# Sheet1.net
KiCad netlist of a schematic drawn in Altium Designer
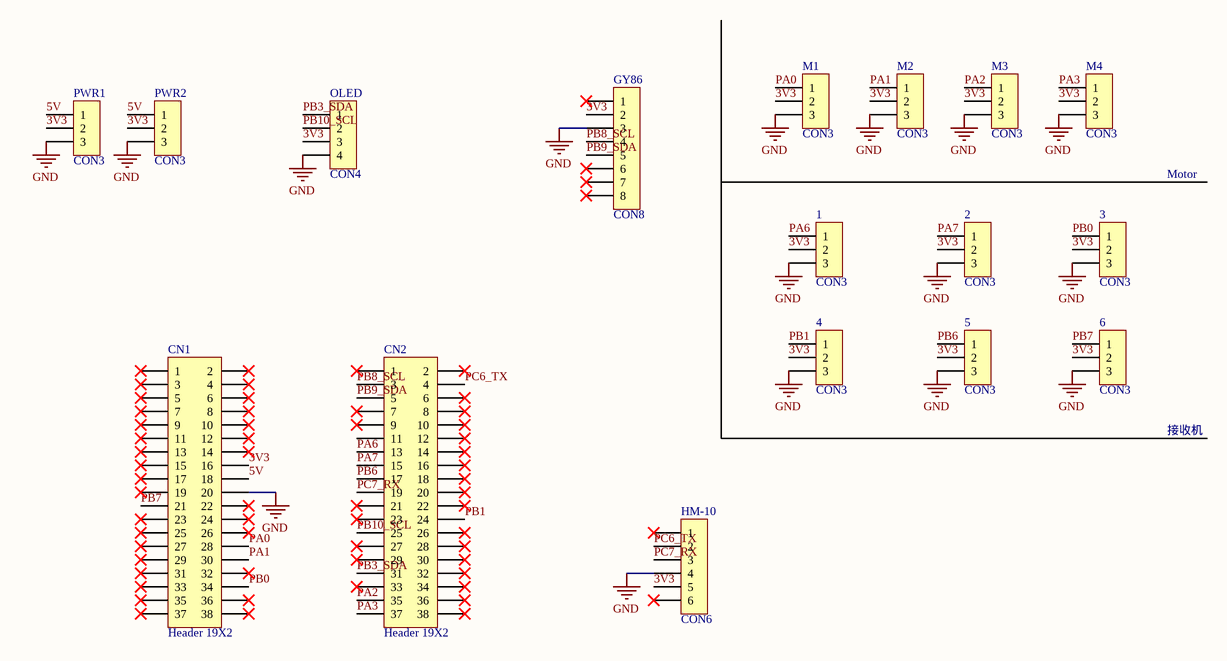
[diagram p0: Sheet1.SchDoc]

(export (version "E")
  (design (tool "Eeschema 10.0.6"))
  (components
    (comp (ref "1") (value "CON3") (footprint "HDR2.54-M-LI-3P") (libsource (lib "常用元件库") (part "CON3")))
    (comp (ref "2") (value "CON3") (footprint "HDR2.54-M-LI-3P") (libsource (lib "常用元件库") (part "CON3")))
    (comp (ref "3") (value "CON3") (footprint "HDR2.54-M-LI-3P") (libsource (lib "常用元件库") (part "CON3")))
    (comp (ref "4") (value "CON3") (footprint "HDR2.54-M-LI-3P") (libsource (lib "常用元件库") (part "CON3")))
    (comp (ref "5") (value "CON3") (footprint "HDR2.54-M-LI-3P") (libsource (lib "常用元件库") (part "CON3")))
    (comp (ref "6") (value "CON3") (footprint "HDR2.54-M-LI-3P") (libsource (lib "常用元件库") (part "CON3")))
    (comp (ref "CN1")
      (value "Header 19X2")
      (footprint "HDR2.54-LI-2x19P")
      (description "Header, 19-Pin, Dual row")
      (fields (field (name "PUBLISHER") "Altium Limited"))
      (libsource (lib "Nucleo_64_1") (part "Header 19X2"))
    )
    (comp (ref "CN2")
      (value "Header 19X2")
      (footprint "HDR2.54-LI-2x19P")
      (description "Header, 19-Pin, Dual row")
      (fields (field (name "PUBLISHER") "Altium Limited"))
      (libsource (lib "Nucleo_64_1") (part "Header 19X2"))
    )
    (comp (ref "GY86") (value "CON8") (footprint "HDR2.54-M-LI-8P") (libsource (lib "常用元件库") (part "CON8")))
    (comp (ref "HM-10") (value "CON6") (footprint "HDR2.54-M-LI-6P") (libsource (lib "常用元件库") (part "CON6")))
    (comp (ref "M1") (value "CON3") (footprint "HDR2.54-M-LI-3P") (libsource (lib "常用元件库") (part "CON3")))
    (comp (ref "M2") (value "CON3") (footprint "HDR2.54-M-LI-3P") (libsource (lib "常用元件库") (part "CON3")))
    (comp (ref "M3") (value "CON3") (footprint "HDR2.54-M-LI-3P") (libsource (lib "常用元件库") (part "CON3")))
    (comp (ref "M4") (value "CON3") (footprint "HDR2.54-M-LI-3P") (libsource (lib "常用元件库") (part "CON3")))
    (comp (ref "OLED") (value "CON4") (footprint "HDR2.54-M-LI-4P") (libsource (lib "常用元件库") (part "CON4")))
    (comp (ref "PWR1") (value "CON3") (footprint "HDR2.54-M-LI-3P") (libsource (lib "常用元件库") (part "CON3")))
    (comp (ref "PWR2") (value "CON3") (footprint "HDR2.54-M-LI-3P") (libsource (lib "常用元件库") (part "CON3")))
  )
  (nets
    (net (code "1") (name "/3V3") (class "Default")
      (node (ref "1") (pin "2") (pinfunction "2_2") (pintype "passive"))
      (node (ref "2") (pin "2") (pinfunction "2_2") (pintype "passive"))
      (node (ref "3") (pin "2") (pinfunction "2_2") (pintype "passive"))
      (node (ref "4") (pin "2") (pinfunction "2_2") (pintype "passive"))
      (node (ref "5") (pin "2") (pinfunction "2_2") (pintype "passive"))
      (node (ref "6") (pin "2") (pinfunction "2_2") (pintype "passive"))
      (node (ref "CN1") (pin "16") (pinfunction "16_16") (pintype "passive"))
      (node (ref "GY86") (pin "2") (pinfunction "2_2") (pintype "passive"))
      (node (ref "HM-10") (pin "5") (pinfunction "5_5") (pintype "passive"))
      (node (ref "M1") (pin "2") (pinfunction "2_2") (pintype "passive"))
      (node (ref "M2") (pin "2") (pinfunction "2_2") (pintype "passive"))
      (node (ref "M3") (pin "2") (pinfunction "2_2") (pintype "passive"))
      (node (ref "M4") (pin "2") (pinfunction "2_2") (pintype "passive"))
      (node (ref "OLED") (pin "3") (pinfunction "3_3") (pintype "passive"))
      (node (ref "PWR1") (pin "2") (pinfunction "2_2") (pintype "passive"))
      (node (ref "PWR2") (pin "2") (pinfunction "2_2") (pintype "passive"))
    )
    (net (code "2") (name "/5V") (class "Default")
      (node (ref "CN1") (pin "18") (pinfunction "18_18") (pintype "passive"))
      (node (ref "PWR1") (pin "1") (pinfunction "1_1") (pintype "passive"))
      (node (ref "PWR2") (pin "1") (pinfunction "1_1") (pintype "passive"))
    )
    (net (code "3") (name "/PA0") (class "Default")
      (node (ref "CN1") (pin "28") (pinfunction "28_28") (pintype "passive"))
      (node (ref "M1") (pin "1") (pinfunction "1_1") (pintype "passive"))
    )
    (net (code "4") (name "/PA1") (class "Default")
      (node (ref "CN1") (pin "30") (pinfunction "30_30") (pintype "passive"))
      (node (ref "M2") (pin "1") (pinfunction "1_1") (pintype "passive"))
    )
    (net (code "5") (name "/PA2") (class "Default")
      (node (ref "CN2") (pin "35") (pinfunction "35_35") (pintype "passive"))
      (node (ref "M3") (pin "1") (pinfunction "1_1") (pintype "passive"))
    )
    (net (code "6") (name "/PA3") (class "Default")
      (node (ref "CN2") (pin "37") (pinfunction "37_37") (pintype "passive"))
      (node (ref "M4") (pin "1") (pinfunction "1_1") (pintype "passive"))
    )
    (net (code "7") (name "/PA6") (class "Default")
      (node (ref "1") (pin "1") (pinfunction "1_1") (pintype "passive"))
      (node (ref "CN2") (pin "13") (pinfunction "13_13") (pintype "passive"))
    )
    (net (code "8") (name "/PA7") (class "Default")
      (node (ref "2") (pin "1") (pinfunction "1_1") (pintype "passive"))
      (node (ref "CN2") (pin "15") (pinfunction "15_15") (pintype "passive"))
    )
    (net (code "9") (name "/PB0") (class "Default")
      (node (ref "3") (pin "1") (pinfunction "1_1") (pintype "passive"))
      (node (ref "CN1") (pin "34") (pinfunction "34_34") (pintype "passive"))
    )
    (net (code "10") (name "/PB1") (class "Default")
      (node (ref "4") (pin "1") (pinfunction "1_1") (pintype "passive"))
      (node (ref "CN2") (pin "24") (pinfunction "24_24") (pintype "passive"))
    )
    (net (code "11") (name "/PB3_SDA") (class "Default")
      (node (ref "CN2") (pin "31") (pinfunction "31_31") (pintype "passive"))
      (node (ref "OLED") (pin "1") (pinfunction "1_1") (pintype "passive"))
    )
    (net (code "12") (name "/PB6") (class "Default")
      (node (ref "5") (pin "1") (pinfunction "1_1") (pintype "passive"))
      (node (ref "CN2") (pin "17") (pinfunction "17_17") (pintype "passive"))
    )
    (net (code "13") (name "/PB7") (class "Default")
      (node (ref "6") (pin "1") (pinfunction "1_1") (pintype "passive"))
      (node (ref "CN1") (pin "21") (pinfunction "21_21") (pintype "passive"))
    )
    (net (code "14") (name "/PB8_SCL") (class "Default")
      (node (ref "CN2") (pin "3") (pinfunction "3_3") (pintype "passive"))
      (node (ref "GY86") (pin "4") (pinfunction "4_4") (pintype "passive"))
    )
    (net (code "15") (name "/PB9_SDA") (class "Default")
      (node (ref "CN2") (pin "5") (pinfunction "5_5") (pintype "passive"))
      (node (ref "GY86") (pin "5") (pinfunction "5_5") (pintype "passive"))
    )
    (net (code "16") (name "/PB10_SCL") (class "Default")
      (node (ref "CN2") (pin "25") (pinfunction "25_25") (pintype "passive"))
      (node (ref "OLED") (pin "2") (pinfunction "2_2") (pintype "passive"))
    )
    (net (code "17") (name "/PC6_TX") (class "Default")
      (node (ref "CN2") (pin "4") (pinfunction "4_4") (pintype "passive"))
      (node (ref "HM-10") (pin "2") (pinfunction "2_2") (pintype "passive"))
    )
    (net (code "18") (name "/PC7_RX") (class "Default")
      (node (ref "CN2") (pin "19") (pinfunction "19_19") (pintype "passive"))
      (node (ref "HM-10") (pin "3") (pinfunction "3_3") (pintype "passive"))
    )
    (net (code "19") (name "GND") (class "Default")
      (node (ref "1") (pin "3") (pinfunction "3_3") (pintype "passive"))
      (node (ref "2") (pin "3") (pinfunction "3_3") (pintype "passive"))
      (node (ref "3") (pin "3") (pinfunction "3_3") (pintype "passive"))
      (node (ref "4") (pin "3") (pinfunction "3_3") (pintype "passive"))
      (node (ref "5") (pin "3") (pinfunction "3_3") (pintype "passive"))
      (node (ref "6") (pin "3") (pinfunction "3_3") (pintype "passive"))
      (node (ref "CN1") (pin "20") (pinfunction "20_20") (pintype "passive"))
      (node (ref "GY86") (pin "3") (pinfunction "3_3") (pintype "passive"))
      (node (ref "HM-10") (pin "4") (pinfunction "4_4") (pintype "passive"))
      (node (ref "M1") (pin "3") (pinfunction "3_3") (pintype "passive"))
      (node (ref "M2") (pin "3") (pinfunction "3_3") (pintype "passive"))
      (node (ref "M3") (pin "3") (pinfunction "3_3") (pintype "passive"))
      (node (ref "M4") (pin "3") (pinfunction "3_3") (pintype "passive"))
      (node (ref "OLED") (pin "4") (pinfunction "4_4") (pintype "passive"))
      (node (ref "PWR1") (pin "3") (pinfunction "3_3") (pintype "passive"))
      (node (ref "PWR2") (pin "3") (pinfunction "3_3") (pintype "passive"))
    )
    (net (code "20") (name "unconnected-(CN1-Pad1)") (class "Default")
      (node (ref "CN1") (pin "1") (pinfunction "1_1") (pintype "passive+no_connect"))
    )
    (net (code "21") (name "unconnected-(CN1-Pad2)") (class "Default")
      (node (ref "CN1") (pin "2") (pinfunction "2_2") (pintype "passive+no_connect"))
    )
    (net (code "22") (name "unconnected-(CN1-Pad3)") (class "Default")
      (node (ref "CN1") (pin "3") (pinfunction "3_3") (pintype "passive+no_connect"))
    )
    (net (code "23") (name "unconnected-(CN1-Pad4)") (class "Default")
      (node (ref "CN1") (pin "4") (pinfunction "4_4") (pintype "passive+no_connect"))
    )
    (net (code "24") (name "unconnected-(CN1-Pad5)") (class "Default")
      (node (ref "CN1") (pin "5") (pinfunction "5_5") (pintype "passive+no_connect"))
    )
    (net (code "25") (name "unconnected-(CN1-Pad6)") (class "Default")
      (node (ref "CN1") (pin "6") (pinfunction "6_6") (pintype "passive+no_connect"))
    )
    (net (code "26") (name "unconnected-(CN1-Pad7)") (class "Default")
      (node (ref "CN1") (pin "7") (pinfunction "7_7") (pintype "passive+no_connect"))
    )
    (net (code "27") (name "unconnected-(CN1-Pad8)") (class "Default")
      (node (ref "CN1") (pin "8") (pinfunction "8_8") (pintype "passive+no_connect"))
    )
    (net (code "28") (name "unconnected-(CN1-Pad9)") (class "Default")
      (node (ref "CN1") (pin "9") (pinfunction "9_9") (pintype "passive+no_connect"))
    )
    (net (code "29") (name "unconnected-(CN1-Pad10)") (class "Default")
      (node (ref "CN1") (pin "10") (pinfunction "10_10") (pintype "passive+no_connect"))
    )
    (net (code "30") (name "unconnected-(CN1-Pad11)") (class "Default")
      (node (ref "CN1") (pin "11") (pinfunction "11_11") (pintype "passive+no_connect"))
    )
    (net (code "31") (name "unconnected-(CN1-Pad12)") (class "Default")
      (node (ref "CN1") (pin "12") (pinfunction "12_12") (pintype "passive+no_connect"))
    )
    (net (code "32") (name "unconnected-(CN1-Pad13)") (class "Default")
      (node (ref "CN1") (pin "13") (pinfunction "13_13") (pintype "passive+no_connect"))
    )
    (net (code "33") (name "unconnected-(CN1-Pad14)") (class "Default")
      (node (ref "CN1") (pin "14") (pinfunction "14_14") (pintype "passive+no_connect"))
    )
    (net (code "34") (name "unconnected-(CN1-Pad15)") (class "Default")
      (node (ref "CN1") (pin "15") (pinfunction "15_15") (pintype "passive+no_connect"))
    )
    (net (code "35") (name "unconnected-(CN1-Pad17)") (class "Default")
      (node (ref "CN1") (pin "17") (pinfunction "17_17") (pintype "passive+no_connect"))
    )
    (net (code "36") (name "unconnected-(CN1-Pad19)") (class "Default")
      (node (ref "CN1") (pin "19") (pinfunction "19_19") (pintype "passive+no_connect"))
    )
    (net (code "37") (name "unconnected-(CN1-Pad22)") (class "Default")
      (node (ref "CN1") (pin "22") (pinfunction "22_22") (pintype "passive+no_connect"))
    )
    (net (code "38") (name "unconnected-(CN1-Pad23)") (class "Default")
      (node (ref "CN1") (pin "23") (pinfunction "23_23") (pintype "passive+no_connect"))
    )
    (net (code "39") (name "unconnected-(CN1-Pad24)") (class "Default")
      (node (ref "CN1") (pin "24") (pinfunction "24_24") (pintype "passive+no_connect"))
    )
    (net (code "40") (name "unconnected-(CN1-Pad25)") (class "Default")
      (node (ref "CN1") (pin "25") (pinfunction "25_25") (pintype "passive+no_connect"))
    )
    (net (code "41") (name "unconnected-(CN1-Pad26)") (class "Default")
      (node (ref "CN1") (pin "26") (pinfunction "26_26") (pintype "passive+no_connect"))
    )
    (net (code "42") (name "unconnected-(CN1-Pad27)") (class "Default")
      (node (ref "CN1") (pin "27") (pinfunction "27_27") (pintype "passive+no_connect"))
    )
    (net (code "43") (name "unconnected-(CN1-Pad29)") (class "Default")
      (node (ref "CN1") (pin "29") (pinfunction "29_29") (pintype "passive+no_connect"))
    )
    (net (code "44") (name "unconnected-(CN1-Pad31)") (class "Default")
      (node (ref "CN1") (pin "31") (pinfunction "31_31") (pintype "passive+no_connect"))
    )
    (net (code "45") (name "unconnected-(CN1-Pad32)") (class "Default")
      (node (ref "CN1") (pin "32") (pinfunction "32_32") (pintype "passive+no_connect"))
    )
    (net (code "46") (name "unconnected-(CN1-Pad33)") (class "Default")
      (node (ref "CN1") (pin "33") (pinfunction "33_33") (pintype "passive+no_connect"))
    )
    (net (code "47") (name "unconnected-(CN1-Pad35)") (class "Default")
      (node (ref "CN1") (pin "35") (pinfunction "35_35") (pintype "passive+no_connect"))
    )
    (net (code "48") (name "unconnected-(CN1-Pad36)") (class "Default")
      (node (ref "CN1") (pin "36") (pinfunction "36_36") (pintype "passive+no_connect"))
    )
    (net (code "49") (name "unconnected-(CN1-Pad37)") (class "Default")
      (node (ref "CN1") (pin "37") (pinfunction "37_37") (pintype "passive+no_connect"))
    )
    (net (code "50") (name "unconnected-(CN1-Pad38)") (class "Default")
      (node (ref "CN1") (pin "38") (pinfunction "38_38") (pintype "passive+no_connect"))
    )
    (net (code "51") (name "unconnected-(CN2-Pad1)") (class "Default")
      (node (ref "CN2") (pin "1") (pinfunction "1_1") (pintype "passive+no_connect"))
    )
    (net (code "52") (name "unconnected-(CN2-Pad2)") (class "Default")
      (node (ref "CN2") (pin "2") (pinfunction "2_2") (pintype "passive+no_connect"))
    )
    (net (code "53") (name "unconnected-(CN2-Pad6)") (class "Default")
      (node (ref "CN2") (pin "6") (pinfunction "6_6") (pintype "passive+no_connect"))
    )
    (net (code "54") (name "unconnected-(CN2-Pad7)") (class "Default")
      (node (ref "CN2") (pin "7") (pinfunction "7_7") (pintype "passive+no_connect"))
    )
    (net (code "55") (name "unconnected-(CN2-Pad8)") (class "Default")
      (node (ref "CN2") (pin "8") (pinfunction "8_8") (pintype "passive+no_connect"))
    )
    (net (code "56") (name "unconnected-(CN2-Pad9)") (class "Default")
      (node (ref "CN2") (pin "9") (pinfunction "9_9") (pintype "passive+no_connect"))
    )
    (net (code "57") (name "unconnected-(CN2-Pad10)") (class "Default")
      (node (ref "CN2") (pin "10") (pinfunction "10_10") (pintype "passive+no_connect"))
    )
    (net (code "58") (name "unconnected-(CN2-Pad11)") (class "Default")
      (node (ref "CN2") (pin "11") (pinfunction "11_11") (pintype "passive"))
    )
    (net (code "59") (name "unconnected-(CN2-Pad12)") (class "Default")
      (node (ref "CN2") (pin "12") (pinfunction "12_12") (pintype "passive+no_connect"))
    )
    (net (code "60") (name "unconnected-(CN2-Pad14)") (class "Default")
      (node (ref "CN2") (pin "14") (pinfunction "14_14") (pintype "passive+no_connect"))
    )
    (net (code "61") (name "unconnected-(CN2-Pad16)") (class "Default")
      (node (ref "CN2") (pin "16") (pinfunction "16_16") (pintype "passive+no_connect"))
    )
    (net (code "62") (name "unconnected-(CN2-Pad18)") (class "Default")
      (node (ref "CN2") (pin "18") (pinfunction "18_18") (pintype "passive+no_connect"))
    )
    (net (code "63") (name "unconnected-(CN2-Pad20)") (class "Default")
      (node (ref "CN2") (pin "20") (pinfunction "20_20") (pintype "passive+no_connect"))
    )
    (net (code "64") (name "unconnected-(CN2-Pad21)") (class "Default")
      (node (ref "CN2") (pin "21") (pinfunction "21_21") (pintype "passive+no_connect"))
    )
    (net (code "65") (name "unconnected-(CN2-Pad22)") (class "Default")
      (node (ref "CN2") (pin "22") (pinfunction "22_22") (pintype "passive+no_connect"))
    )
    (net (code "66") (name "unconnected-(CN2-Pad23)") (class "Default")
      (node (ref "CN2") (pin "23") (pinfunction "23_23") (pintype "passive+no_connect"))
    )
    (net (code "67") (name "unconnected-(CN2-Pad26)") (class "Default")
      (node (ref "CN2") (pin "26") (pinfunction "26_26") (pintype "passive+no_connect"))
    )
    (net (code "68") (name "unconnected-(CN2-Pad27)") (class "Default")
      (node (ref "CN2") (pin "27") (pinfunction "27_27") (pintype "passive+no_connect"))
    )
    (net (code "69") (name "unconnected-(CN2-Pad28)") (class "Default")
      (node (ref "CN2") (pin "28") (pinfunction "28_28") (pintype "passive+no_connect"))
    )
    (net (code "70") (name "unconnected-(CN2-Pad29)") (class "Default")
      (node (ref "CN2") (pin "29") (pinfunction "29_29") (pintype "passive+no_connect"))
    )
    (net (code "71") (name "unconnected-(CN2-Pad30)") (class "Default")
      (node (ref "CN2") (pin "30") (pinfunction "30_30") (pintype "passive+no_connect"))
    )
    (net (code "72") (name "unconnected-(CN2-Pad32)") (class "Default")
      (node (ref "CN2") (pin "32") (pinfunction "32_32") (pintype "passive+no_connect"))
    )
    (net (code "73") (name "unconnected-(CN2-Pad33)") (class "Default")
      (node (ref "CN2") (pin "33") (pinfunction "33_33") (pintype "passive+no_connect"))
    )
    (net (code "74") (name "unconnected-(CN2-Pad34)") (class "Default")
      (node (ref "CN2") (pin "34") (pinfunction "34_34") (pintype "passive+no_connect"))
    )
    (net (code "75") (name "unconnected-(CN2-Pad36)") (class "Default")
      (node (ref "CN2") (pin "36") (pinfunction "36_36") (pintype "passive+no_connect"))
    )
    (net (code "76") (name "unconnected-(CN2-Pad38)") (class "Default")
      (node (ref "CN2") (pin "38") (pinfunction "38_38") (pintype "passive+no_connect"))
    )
    (net (code "77") (name "unconnected-(GY86-Pad1)") (class "Default")
      (node (ref "GY86") (pin "1") (pinfunction "1_1") (pintype "passive+no_connect"))
    )
    (net (code "78") (name "unconnected-(GY86-Pad6)") (class "Default")
      (node (ref "GY86") (pin "6") (pinfunction "6_6") (pintype "passive+no_connect"))
    )
    (net (code "79") (name "unconnected-(GY86-Pad7)") (class "Default")
      (node (ref "GY86") (pin "7") (pinfunction "7_7") (pintype "passive+no_connect"))
    )
    (net (code "80") (name "unconnected-(GY86-Pad8)") (class "Default")
      (node (ref "GY86") (pin "8") (pinfunction "8_8") (pintype "passive+no_connect"))
    )
    (net (code "81") (name "unconnected-(HM-10-Pad1)") (class "Default")
      (node (ref "HM-10") (pin "1") (pinfunction "1_1") (pintype "passive+no_connect"))
    )
    (net (code "82") (name "unconnected-(HM-10-Pad6)") (class "Default")
      (node (ref "HM-10") (pin "6") (pinfunction "6_6") (pintype "passive+no_connect"))
    )
  )
)
